# Schematic_page2.net
KiCad netlist of a schematic drawn in Altium Designer
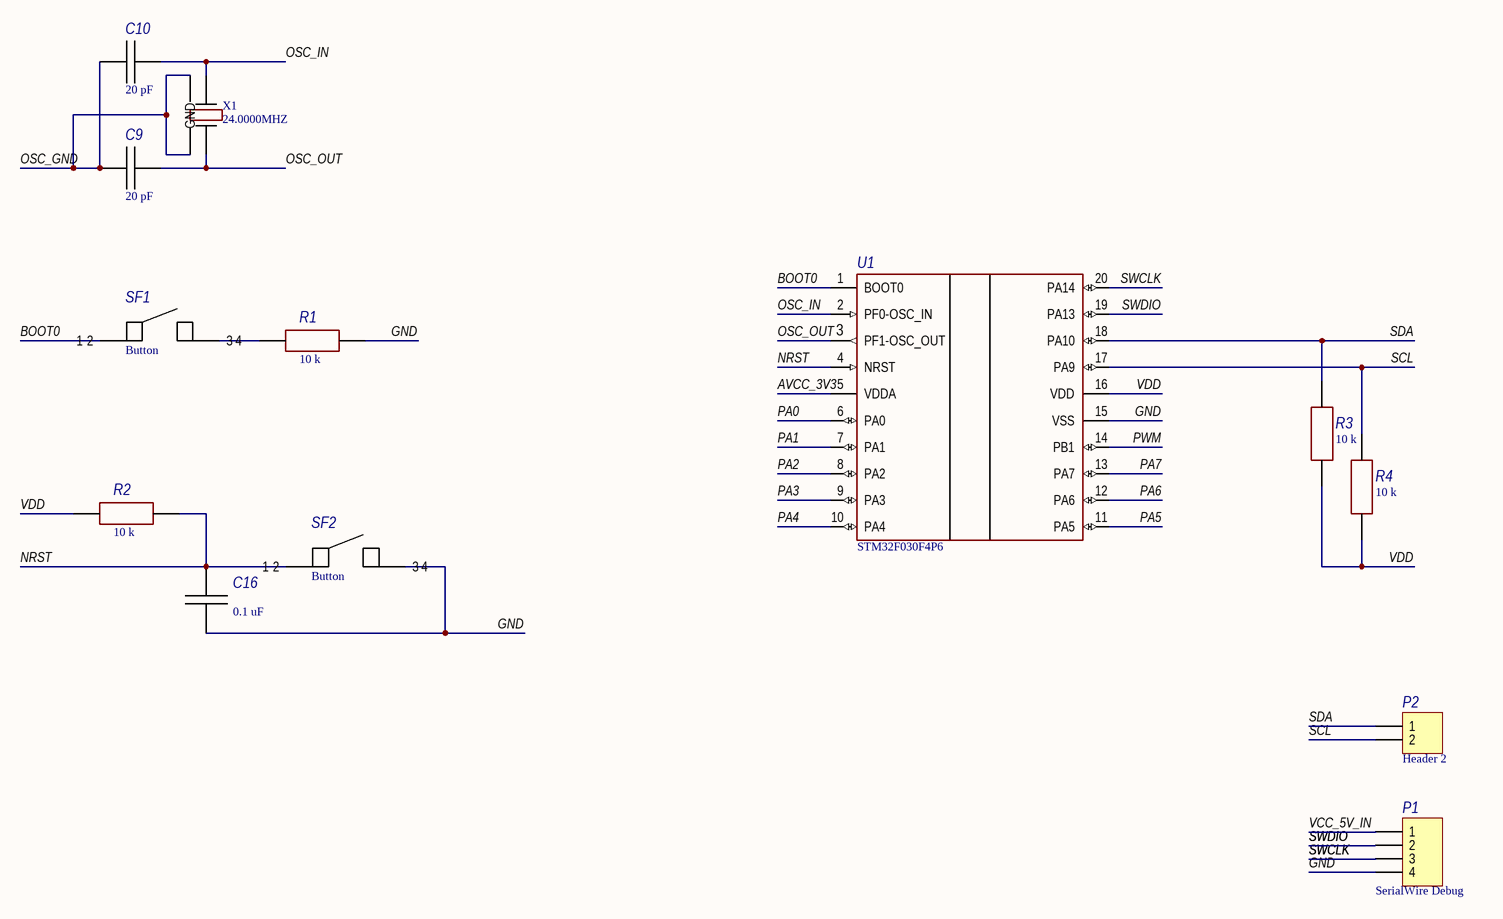
[diagram p0: Schematic_page2.SchDoc]

(export (version "E")
  (design (tool "Eeschema 10.0.6"))
  (components
    (comp (ref "C9") (value "20 pF") (footprint "C0603") (libsource (lib "Linalance_lib") (part "Capasitor")))
    (comp (ref "C10")
      (value "20 pF")
      (footprint "C0603")
      (libsource (lib "Linalance_lib") (part "Capasitor"))
    )
    (comp (ref "C16") (value "0.1 uF") (footprint "C0603") (libsource (lib "") (part "Capasitor_1")))
    (comp (ref "P1")
      (value "SerialWire Debug")
      (footprint "HDR1X4")
      (description "Header, 4-Pin")
      (fields (field (name "PUBLISHER") "Altium Limited"))
      (libsource (lib "Miscellaneous Connectors") (part "Header 4"))
    )
    (comp (ref "P2")
      (value "Header 2")
      (footprint "HDR1X2")
      (description "Header, 2-Pin")
      (fields (field (name "PUBLISHER") "Altium Limited"))
      (libsource (lib "Miscellaneous Connectors") (part "Header 2"))
    )
    (comp (ref "R1") (value "10 k") (footprint "R0603") (libsource (lib "") (part "Resistor_2")))
    (comp (ref "R2") (value "10 k") (footprint "R0603") (libsource (lib "Linalance_lib") (part "Resistor")))
    (comp (ref "R3") (value "10 k") (footprint "R0603") (libsource (lib "") (part "Resistor_1")))
    (comp (ref "R4") (value "10 k") (footprint "R0603") (libsource (lib "") (part "Resistor_1")))
    (comp (ref "SF1")
      (value "Button")
      (footprint "KMR221GLFS")
      (description "SWITCH TACTILE SPST-NO 0.05A 32V")
      (fields (field (name "MANUFACTURER") "C&K"))
      (libsource (lib "Linalance_lib") (part "Button"))
    )
    (comp (ref "SF2")
      (value "Button")
      (footprint "KMR221GLFS")
      (description "SWITCH TACTILE SPST-NO 0.05A 32V")
      (fields (field (name "MANUFACTURER") "C&K"))
      (libsource (lib "Linalance_lib") (part "Button"))
    )
    (comp (ref "U1")
      (value "STM32F030F4P6")
      (footprint "TSSOP-20")
      (description "IC MCU 32BIT 16KB FLASH 20TSSOP")
      (fields (field (name "MANUFACTURER") "STMicroelectronics"))
      (libsource (lib "Linalance_lib") (part "STM32F030F4P6"))
    )
    (comp (ref "X1")
      (value "24.0000MHZ")
      (footprint "TSX-3225")
      (description "CRYSTAL 24.0000MHZ 9PF SMD")
      (fields (field (name "MANUFACTURER") "EPSON"))
      (libsource (lib "Linalance_lib") (part "Crystal"))
    )
  )
  (nets
    (net (code "1") (name "/AVCC_3V3") (class "Default")
      (node (ref "U1") (pin "5") (pinfunction "VDDA_5") (pintype "power_in"))
    )
    (net (code "2") (name "/BOOT0") (class "Default")
      (node (ref "SF1") (pin "1") (pinfunction "1_1") (pintype "passive"))
      (node (ref "SF1") (pin "2") (pinfunction "2_2") (pintype "passive"))
      (node (ref "U1") (pin "1") (pinfunction "BOOT0_1") (pintype "passive"))
    )
    (net (code "3") (name "/GND") (class "Default")
      (node (ref "C16") (pin "2") (pintype "passive"))
      (node (ref "P1") (pin "4") (pinfunction "4_4") (pintype "passive"))
      (node (ref "R1") (pin "1") (pintype "passive"))
      (node (ref "SF2") (pin "4") (pinfunction "4_4") (pintype "passive"))
      (node (ref "U1") (pin "15") (pinfunction "VSS_15") (pintype "power_in"))
    )
    (net (code "4") (name "/NRST") (class "Default")
      (node (ref "C16") (pin "1") (pintype "passive"))
      (node (ref "R2") (pin "2") (pintype "passive"))
      (node (ref "SF2") (pin "1") (pinfunction "1_1") (pintype "passive"))
      (node (ref "SF2") (pin "2") (pinfunction "2_2") (pintype "passive"))
      (node (ref "U1") (pin "4") (pinfunction "NRST_4") (pintype "input"))
    )
    (net (code "5") (name "/OSC_GND") (class "Default")
      (node (ref "C10") (pin "2") (pintype "passive"))
      (node (ref "C9") (pin "2") (pintype "passive"))
      (node (ref "X1") (pin "2") (pinfunction "GND_2") (pintype "passive"))
      (node (ref "X1") (pin "4") (pinfunction "GND_4") (pintype "passive"))
    )
    (net (code "6") (name "/OSC_IN") (class "Default")
      (node (ref "C10") (pin "1") (pintype "passive"))
      (node (ref "U1") (pin "2") (pinfunction "PF0-OSC_IN_2") (pintype "input"))
      (node (ref "X1") (pin "1") (pintype "passive"))
    )
    (net (code "7") (name "/OSC_OUT") (class "Default")
      (node (ref "C9") (pin "1") (pintype "passive"))
      (node (ref "U1") (pin "3") (pinfunction "PF1-OSC_OUT_3") (pintype "output"))
      (node (ref "X1") (pin "3") (pintype "passive"))
    )
    (net (code "8") (name "/PA0") (class "Default")
      (node (ref "U1") (pin "6") (pinfunction "PA0_6") (pintype "bidirectional"))
    )
    (net (code "9") (name "/PA1") (class "Default")
      (node (ref "U1") (pin "7") (pinfunction "PA1_7") (pintype "bidirectional"))
    )
    (net (code "10") (name "/PA2") (class "Default")
      (node (ref "U1") (pin "8") (pinfunction "PA2_8") (pintype "bidirectional"))
    )
    (net (code "11") (name "/PA3") (class "Default")
      (node (ref "U1") (pin "9") (pinfunction "PA3_9") (pintype "bidirectional"))
    )
    (net (code "12") (name "/PA4") (class "Default")
      (node (ref "U1") (pin "10") (pinfunction "PA4_10") (pintype "bidirectional"))
    )
    (net (code "13") (name "/PA5") (class "Default")
      (node (ref "U1") (pin "11") (pinfunction "PA5_11") (pintype "bidirectional"))
    )
    (net (code "14") (name "/PA6") (class "Default")
      (node (ref "U1") (pin "12") (pinfunction "PA6_12") (pintype "bidirectional"))
    )
    (net (code "15") (name "/PA7") (class "Default")
      (node (ref "U1") (pin "13") (pinfunction "PA7_13") (pintype "bidirectional"))
    )
    (net (code "16") (name "/PWM") (class "Default")
      (node (ref "U1") (pin "14") (pinfunction "PB1_14") (pintype "bidirectional"))
    )
    (net (code "17") (name "/SCL") (class "Default")
      (node (ref "P2") (pin "2") (pinfunction "2_2") (pintype "passive"))
      (node (ref "R4") (pin "2") (pintype "passive"))
      (node (ref "U1") (pin "17") (pinfunction "PA9_17") (pintype "bidirectional"))
    )
    (net (code "18") (name "/SDA") (class "Default")
      (node (ref "P2") (pin "1") (pinfunction "1_1") (pintype "passive"))
      (node (ref "R3") (pin "2") (pintype "passive"))
      (node (ref "U1") (pin "18") (pinfunction "PA10_18") (pintype "bidirectional"))
    )
    (net (code "19") (name "/SWCLK") (class "Default")
      (node (ref "P1") (pin "3") (pinfunction "3_3") (pintype "passive"))
      (node (ref "U1") (pin "20") (pinfunction "PA14_20") (pintype "bidirectional"))
    )
    (net (code "20") (name "/SWDIO") (class "Default")
      (node (ref "P1") (pin "2") (pinfunction "2_2") (pintype "passive"))
      (node (ref "U1") (pin "19") (pinfunction "PA13_19") (pintype "bidirectional"))
    )
    (net (code "21") (name "/VCC_5V_IN") (class "Default")
      (node (ref "P1") (pin "1") (pinfunction "1_1") (pintype "passive"))
    )
    (net (code "22") (name "/VDD") (class "Default")
      (node (ref "R2") (pin "1") (pintype "passive"))
      (node (ref "R3") (pin "1") (pintype "passive"))
      (node (ref "R4") (pin "1") (pintype "passive"))
      (node (ref "U1") (pin "16") (pinfunction "VDD_16") (pintype "power_in"))
    )
    (net (code "23") (name "Net-(R1-Pad2)") (class "Default")
      (node (ref "R1") (pin "2") (pintype "passive"))
      (node (ref "SF1") (pin "4") (pinfunction "4_4") (pintype "passive"))
    )
    (net (code "24") (name "unconnected-(SF1-Pad3)") (class "Default")
      (node (ref "SF1") (pin "3") (pinfunction "3_3") (pintype "passive"))
    )
    (net (code "25") (name "unconnected-(SF2-Pad3)") (class "Default")
      (node (ref "SF2") (pin "3") (pinfunction "3_3") (pintype "passive"))
    )
  )
)
